# 1_iip_charge.net
KiCad netlist of a schematic drawn in Altium Designer
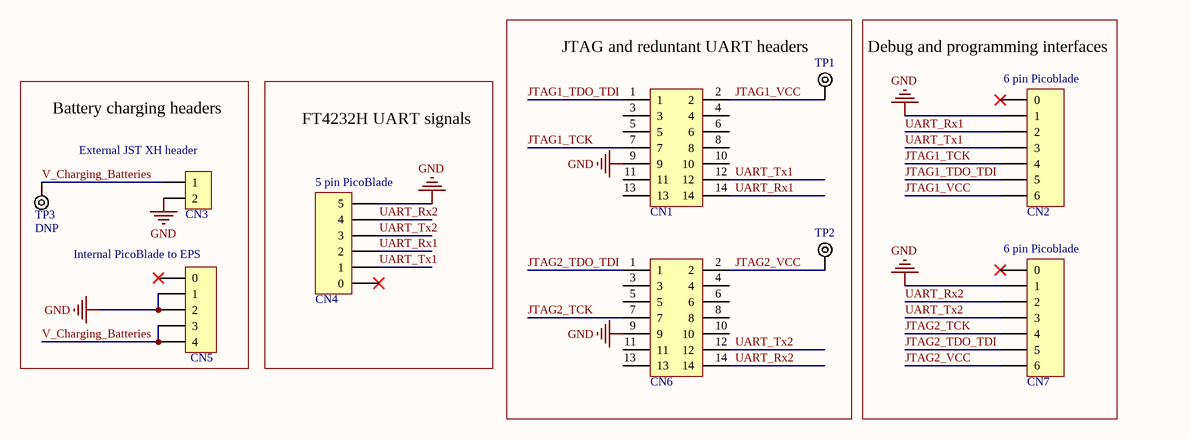
[diagram p0: 1_iip_charge.SchDoc]

(export (version "E")
  (design (tool "Eeschema 10.0.6"))
  (components
    (comp (ref "CN1")
      (value "7 POS dual line Pin Header 2.54mm")
      (footprint "CONN HEADER VERT 14POS 2.54MM")
      (description "Headers & Wire Housings 07+07 DIL VERTICAL PIN HEADER GOLD HT")
      (fields (field (name "MANUFACTURER") "Harwin") (field (name "MANUFACTURER PART NUMBER") "M20-9980745"))
      (libsource (lib "IB_floripasat2") (part "M20-9980745"))
    )
    (comp (ref "CN2")
      (value "6 pin Picoblade")
      (footprint "PICO BLADE 0533980671")
      (description "1.25mm Pitch PicoBlade™ Header, Surface Mount, Vertical, 6 Circuits")
      (fields (field (name "MANUFACTURER") "Molex") (field (name "MANUFACTURER PART NUMBER") "53398-0671"))
      (libsource (lib "IB_floripasat2") (part "53398-0671"))
    )
    (comp (ref "CN3")
      (value "JST 2 position header 2.5mm")
      (footprint "B2B-XH-A-M(LF)(SN)")
      (description "CONN HEADER TOP 2POS 2.5MM GRN")
      (fields
        (field (name "MANUFACTURER") "JST")
        (field (name "MANUFACTURER PART NUMBER") "B2B-XH-A-M(LF)(SN)")
      )
      (libsource (lib "IB_floripasat2") (part "B2B-XH-A-M(LF)(SN)"))
    )
    (comp (ref "CN4")
      (value "5 pin PicoBlade")
      (footprint "PICO BLADE 0533980571")
      (description "Wire-To-Board Connector, Vertical, PicoBlade 53398 Series, Surface Mount, Header, 5, 1.25 mm")
      (fields (field (name "MANUFACTURER") "Molex") (field (name "MANUFACTURER PART NUMBER") "53398-0571"))
      (libsource (lib "IB_floripasat2") (part "53398-0571"))
    )
    (comp (ref "CN5")
      (value "4 pin Picoblade")
      (footprint "PICO BLADE 0533980471")
      (description "Connector Header Surface Mount 4 position 0.049\" (1.25mm)")
      (fields (field (name "MANUFACTURER") "Molex") (field (name "MANUFACTURER PART NUMBER") "53398-0471"))
      (libsource (lib "IB_floripasat2") (part "0533980471"))
    )
    (comp (ref "CN6")
      (value "7 POS dual line Pin Header 2.54mm")
      (footprint "CONN HEADER VERT 14POS 2.54MM")
      (description "Headers & Wire Housings 07+07 DIL VERTICAL PIN HEADER GOLD HT")
      (fields (field (name "MANUFACTURER") "Harwin") (field (name "MANUFACTURER PART NUMBER") "M20-9980745"))
      (libsource (lib "IB_floripasat2") (part "M20-9980745"))
    )
    (comp (ref "CN7")
      (value "6 pin Picoblade")
      (footprint "PICO BLADE 0533980671")
      (description "1.25mm Pitch PicoBlade™ Header, Surface Mount, Vertical, 6 Circuits")
      (fields (field (name "MANUFACTURER") "Molex") (field (name "MANUFACTURER PART NUMBER") "53398-0671"))
      (libsource (lib "IB_floripasat2") (part "53398-0671"))
    )
    (comp (ref "TP1")
      (value "DNP")
      (footprint "TEST POINT PTH")
      (description "TEST POINT PAD")
      (libsource (lib "IB_floripasat2") (part "Test Point PTH"))
    )
    (comp (ref "TP2")
      (value "DNP")
      (footprint "TEST POINT PTH")
      (description "TEST POINT PAD")
      (libsource (lib "IB_floripasat2") (part "Test Point PTH"))
    )
    (comp (ref "TP3")
      (value "DNP")
      (footprint "TEST POINT PTH")
      (description "TEST POINT PAD")
      (libsource (lib "IB_floripasat2") (part "Test Point PTH"))
    )
  )
  (nets
    (net (code "1") (name "/JTAG1_TCK") (class "Default")
      (node (ref "CN1") (pin "7") (pinfunction "7_7") (pintype "passive"))
      (node (ref "CN2") (pin "4") (pinfunction "4_4") (pintype "passive"))
    )
    (net (code "2") (name "/JTAG1_TDO_TDI") (class "Default")
      (node (ref "CN1") (pin "1") (pinfunction "1_1") (pintype "passive"))
      (node (ref "CN2") (pin "5") (pinfunction "5_5") (pintype "passive"))
    )
    (net (code "3") (name "/JTAG1_VCC") (class "Default")
      (node (ref "CN1") (pin "2") (pinfunction "2_2") (pintype "passive"))
      (node (ref "CN2") (pin "6") (pinfunction "6_6") (pintype "passive"))
      (node (ref "TP1") (pin "1") (pinfunction "1_1") (pintype "passive"))
    )
    (net (code "4") (name "/JTAG2_TCK") (class "Default")
      (node (ref "CN6") (pin "7") (pinfunction "7_7") (pintype "passive"))
      (node (ref "CN7") (pin "4") (pinfunction "4_4") (pintype "passive"))
    )
    (net (code "5") (name "/JTAG2_TDO_TDI") (class "Default")
      (node (ref "CN6") (pin "1") (pinfunction "1_1") (pintype "passive"))
      (node (ref "CN7") (pin "5") (pinfunction "5_5") (pintype "passive"))
    )
    (net (code "6") (name "/JTAG2_VCC") (class "Default")
      (node (ref "CN6") (pin "2") (pinfunction "2_2") (pintype "passive"))
      (node (ref "CN7") (pin "6") (pinfunction "6_6") (pintype "passive"))
      (node (ref "TP2") (pin "1") (pinfunction "1_1") (pintype "passive"))
    )
    (net (code "7") (name "/UART_Rx1") (class "Default")
      (node (ref "CN1") (pin "14") (pinfunction "14_14") (pintype "passive"))
      (node (ref "CN2") (pin "2") (pinfunction "2_2") (pintype "passive"))
      (node (ref "CN4") (pin "2") (pinfunction "2_2") (pintype "passive"))
    )
    (net (code "8") (name "/UART_Rx2") (class "Default")
      (node (ref "CN4") (pin "4") (pinfunction "4_4") (pintype "passive"))
      (node (ref "CN6") (pin "14") (pinfunction "14_14") (pintype "passive"))
      (node (ref "CN7") (pin "2") (pinfunction "2_2") (pintype "passive"))
    )
    (net (code "9") (name "/UART_Tx1") (class "Default")
      (node (ref "CN1") (pin "12") (pinfunction "12_12") (pintype "passive"))
      (node (ref "CN2") (pin "3") (pinfunction "3_3") (pintype "passive"))
      (node (ref "CN4") (pin "1") (pinfunction "1_1") (pintype "passive"))
    )
    (net (code "10") (name "/UART_Tx2") (class "Default")
      (node (ref "CN4") (pin "3") (pinfunction "3_3") (pintype "passive"))
      (node (ref "CN6") (pin "12") (pinfunction "12_12") (pintype "passive"))
      (node (ref "CN7") (pin "3") (pinfunction "3_3") (pintype "passive"))
    )
    (net (code "11") (name "/V_Charging_Batteries") (class "Default")
      (node (ref "CN3") (pin "1") (pinfunction "1_1") (pintype "passive"))
      (node (ref "CN5") (pin "3") (pinfunction "3_3") (pintype "passive"))
      (node (ref "CN5") (pin "4") (pinfunction "4_4") (pintype "passive"))
      (node (ref "TP3") (pin "1") (pinfunction "1_1") (pintype "passive"))
    )
    (net (code "12") (name "GND") (class "Default")
      (node (ref "CN1") (pin "9") (pinfunction "9_9") (pintype "passive"))
      (node (ref "CN2") (pin "1") (pinfunction "1_1") (pintype "passive"))
      (node (ref "CN3") (pin "2") (pinfunction "2_2") (pintype "passive"))
      (node (ref "CN4") (pin "5") (pinfunction "5_5") (pintype "passive"))
      (node (ref "CN5") (pin "1") (pinfunction "1_1") (pintype "passive"))
      (node (ref "CN5") (pin "2") (pinfunction "2_2") (pintype "passive"))
      (node (ref "CN6") (pin "9") (pinfunction "9_9") (pintype "passive"))
      (node (ref "CN7") (pin "1") (pinfunction "1_1") (pintype "passive"))
    )
    (net (code "13") (name "unconnected-(CN1-Pad3)") (class "Default")
      (node (ref "CN1") (pin "3") (pinfunction "3_3") (pintype "passive"))
    )
    (net (code "14") (name "unconnected-(CN1-Pad4)") (class "Default")
      (node (ref "CN1") (pin "4") (pinfunction "4_4") (pintype "passive"))
    )
    (net (code "15") (name "unconnected-(CN1-Pad5)") (class "Default")
      (node (ref "CN1") (pin "5") (pinfunction "5_5") (pintype "passive"))
    )
    (net (code "16") (name "unconnected-(CN1-Pad6)") (class "Default")
      (node (ref "CN1") (pin "6") (pinfunction "6_6") (pintype "passive"))
    )
    (net (code "17") (name "unconnected-(CN1-Pad8)") (class "Default")
      (node (ref "CN1") (pin "8") (pinfunction "8_8") (pintype "passive"))
    )
    (net (code "18") (name "unconnected-(CN1-Pad10)") (class "Default")
      (node (ref "CN1") (pin "10") (pinfunction "10_10") (pintype "passive"))
    )
    (net (code "19") (name "unconnected-(CN1-Pad11)") (class "Default")
      (node (ref "CN1") (pin "11") (pinfunction "11_11") (pintype "passive"))
    )
    (net (code "20") (name "unconnected-(CN1-Pad13)") (class "Default")
      (node (ref "CN1") (pin "13") (pinfunction "13_13") (pintype "passive"))
    )
    (net (code "21") (name "unconnected-(CN2-Pad0)") (class "Default")
      (node (ref "CN2") (pin "0") (pinfunction "0_0") (pintype "passive+no_connect"))
    )
    (net (code "22") (name "unconnected-(CN4-Pad0)") (class "Default")
      (node (ref "CN4") (pin "0") (pinfunction "0_0") (pintype "passive+no_connect"))
    )
    (net (code "23") (name "unconnected-(CN5-Pad0)") (class "Default")
      (node (ref "CN5") (pin "0") (pinfunction "0_0") (pintype "passive+no_connect"))
    )
    (net (code "24") (name "unconnected-(CN6-Pad3)") (class "Default")
      (node (ref "CN6") (pin "3") (pinfunction "3_3") (pintype "passive"))
    )
    (net (code "25") (name "unconnected-(CN6-Pad4)") (class "Default")
      (node (ref "CN6") (pin "4") (pinfunction "4_4") (pintype "passive"))
    )
    (net (code "26") (name "unconnected-(CN6-Pad5)") (class "Default")
      (node (ref "CN6") (pin "5") (pinfunction "5_5") (pintype "passive"))
    )
    (net (code "27") (name "unconnected-(CN6-Pad6)") (class "Default")
      (node (ref "CN6") (pin "6") (pinfunction "6_6") (pintype "passive"))
    )
    (net (code "28") (name "unconnected-(CN6-Pad8)") (class "Default")
      (node (ref "CN6") (pin "8") (pinfunction "8_8") (pintype "passive"))
    )
    (net (code "29") (name "unconnected-(CN6-Pad10)") (class "Default")
      (node (ref "CN6") (pin "10") (pinfunction "10_10") (pintype "passive"))
    )
    (net (code "30") (name "unconnected-(CN6-Pad11)") (class "Default")
      (node (ref "CN6") (pin "11") (pinfunction "11_11") (pintype "passive"))
    )
    (net (code "31") (name "unconnected-(CN6-Pad13)") (class "Default")
      (node (ref "CN6") (pin "13") (pinfunction "13_13") (pintype "passive"))
    )
    (net (code "32") (name "unconnected-(CN7-Pad0)") (class "Default")
      (node (ref "CN7") (pin "0") (pinfunction "0_0") (pintype "passive+no_connect"))
    )
  )
)
